# MB1297_RF_Module.net
KiCad netlist of a schematic drawn in Altium Designer
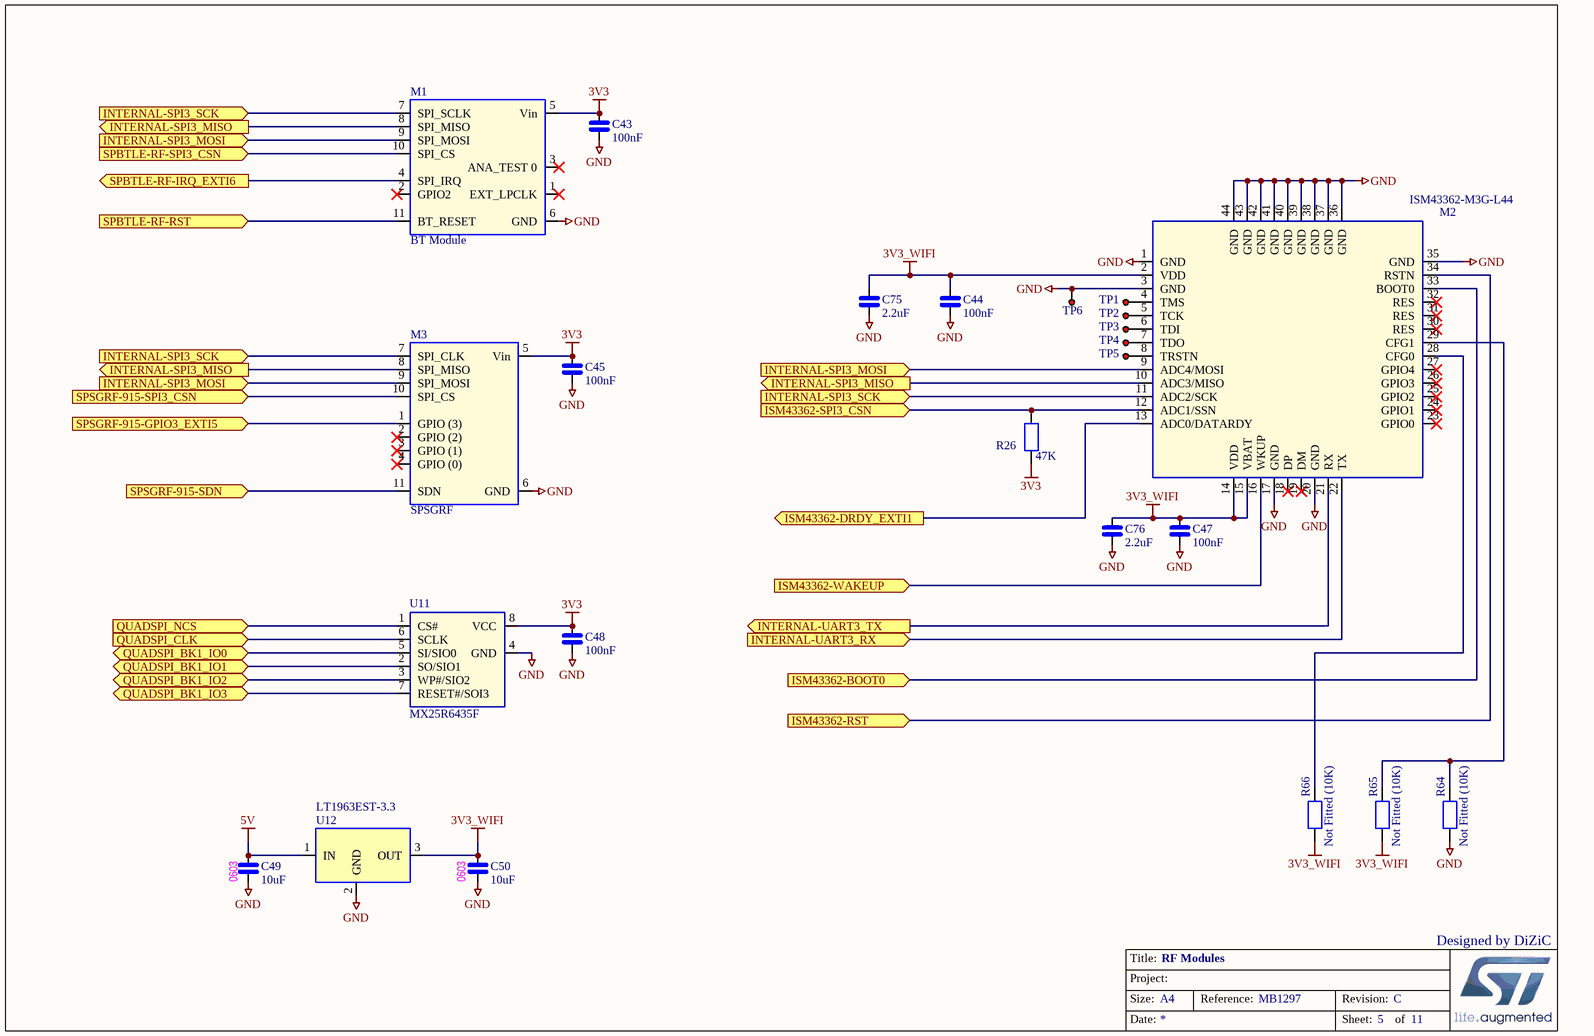
[diagram p0: MB1297_RF_Module.SchDoc]

(export (version "E")
  (design (tool "Eeschema 10.0.6"))
  (components
    (comp (ref "C43")
      (value "100nF")
      (footprint "0402_CAP_NPOL")
      (description "Capacitor_not polarized")
      (libsource (lib "ST_Lib3D") (part "CAP_NPOL"))
    )
    (comp (ref "C44")
      (value "100nF")
      (footprint "0402_CAP_NPOL")
      (description "Capacitor_not polarized")
      (libsource (lib "ST_Lib3D") (part "CAP_NPOL"))
    )
    (comp (ref "C45")
      (value "100nF")
      (footprint "0402_CAP_NPOL")
      (description "Capacitor_not polarized")
      (libsource (lib "ST_Lib3D") (part "CAP_NPOL"))
    )
    (comp (ref "C47")
      (value "100nF")
      (footprint "0402_CAP_NPOL")
      (description "Capacitor_not polarized")
      (libsource (lib "ST_Lib3D") (part "CAP_NPOL"))
    )
    (comp (ref "C48")
      (value "100nF")
      (footprint "0402_CAP_NPOL")
      (description "Capacitor_not polarized")
      (libsource (lib "ST_Lib3D") (part "CAP_NPOL"))
    )
    (comp (ref "C49")
      (value "10uF")
      (footprint "0603_CAP_NPOL")
      (description "Capacitor_not polarized")
      (libsource (lib "ST_Lib3D") (part "CAP_NPOL"))
    )
    (comp (ref "C50")
      (value "10uF")
      (footprint "0603_CAP_NPOL")
      (description "Capacitor_not polarized")
      (libsource (lib "ST_Lib3D") (part "CAP_NPOL"))
    )
    (comp (ref "C75")
      (value "2.2uF")
      (footprint "0603_CAP_NPOL")
      (description "Capacitor_not polarized")
      (libsource (lib "ST_Lib3D") (part "CAP_NPOL"))
    )
    (comp (ref "C76")
      (value "2.2uF")
      (footprint "0603_CAP_NPOL")
      (description "Capacitor_not polarized")
      (libsource (lib "ST_Lib3D") (part "CAP_NPOL"))
    )
    (comp (ref "M1")
      (value "BT Module")
      (footprint "SPBTLE-RF")
      (description "SPBTLE-RF")
      (libsource (lib "ST_Lib3D") (part "SPBTLE-RF"))
    )
    (comp (ref "M2")
      (value "ISM43362-M3G-L44")
      (footprint "ISM43362-M3G-L44")
      (description "ISM43362-M3G-L44 Wifi Module 802.11 bgn")
      (libsource (lib "Phil_Lib3D") (part "ISM43362-M3G-L44"))
    )
    (comp (ref "M3")
      (value "SPSGRF")
      (footprint "SPSGRF")
      (description "SPSGRF-915or SPSGRF-868")
      (libsource (lib "ST_Lib3D") (part "SPSGRF"))
    )
    (comp (ref "R26")
      (value "47K")
      (footprint "0402_RES")
      (description "Resistor")
      (libsource (lib "Lib3D_Altium10_Schlib") (part "RES"))
    )
    (comp (ref "R64")
      (value "Not Fitted (10K)")
      (footprint "0402_RES")
      (description "Resistor")
      (libsource (lib "Lib3D_Altium10_Schlib") (part "RES"))
    )
    (comp (ref "R65")
      (value "Not Fitted (10K)")
      (footprint "0402_RES")
      (description "Resistor")
      (libsource (lib "Lib3D_Altium10_Schlib") (part "RES"))
    )
    (comp (ref "R66")
      (value "Not Fitted (10K)")
      (footprint "0402_RES")
      (description "Resistor")
      (libsource (lib "Lib3D_Altium10_Schlib") (part "RES"))
    )
    (comp (ref "TP1")
      (value "PT")
      (footprint "PTB")
      (description "Point de test")
      (libsource (lib "ST_Lib2D") (part "PT"))
    )
    (comp (ref "TP2")
      (value "PT")
      (footprint "PTB")
      (description "Point de test")
      (libsource (lib "ST_Lib2D") (part "PT"))
    )
    (comp (ref "TP3")
      (value "PT")
      (footprint "PTB")
      (description "Point de test")
      (libsource (lib "ST_Lib2D") (part "PT"))
    )
    (comp (ref "TP4")
      (value "PT")
      (footprint "PTB")
      (description "Point de test")
      (libsource (lib "ST_Lib2D") (part "PT"))
    )
    (comp (ref "TP5")
      (value "PT")
      (footprint "PTB")
      (description "Point de test")
      (libsource (lib "ST_Lib2D") (part "PT"))
    )
    (comp (ref "TP6")
      (value "PT")
      (footprint "PTB")
      (description "Point de test")
      (libsource (lib "ST_Lib2D") (part "PT"))
    )
    (comp (ref "U11")
      (value "MX25R6435F")
      (footprint "SOP8L")
      (description "MX25R6435F Serial Flash Memory 64M")
      (libsource (lib "ST_Lib3D") (part "MX25R6435F"))
    )
    (comp (ref "U12")
      (value "LT1963EST-3.3")
      (footprint "ST_Lib3D:SOT223_SC73")
      (description "LT1963EST-3.3 LDO Low Noise 1.5A fast Transient Response")
      (libsource (lib "ST_Lib3D") (part "LT1963EST-3.3"))
    )
  )
  (nets
    (net (code "1") (name "/INTERNAL-SPI3_MISO") (class "Default")
      (node (ref "M1") (pin "8") (pinfunction "SPI_MISO_8") (pintype "passive"))
      (node (ref "M2") (pin "10") (pinfunction "ADC3/MISO_10") (pintype "passive"))
      (node (ref "M3") (pin "8") (pinfunction "SPI_MISO_8") (pintype "passive"))
    )
    (net (code "2") (name "/INTERNAL-SPI3_MOSI") (class "Default")
      (node (ref "M1") (pin "9") (pinfunction "SPI_MOSI_9") (pintype "passive"))
      (node (ref "M2") (pin "9") (pinfunction "ADC4/MOSI_9") (pintype "passive"))
      (node (ref "M3") (pin "9") (pinfunction "SPI_MOSI_9") (pintype "passive"))
    )
    (net (code "3") (name "/INTERNAL-SPI3_SCK") (class "Default")
      (node (ref "M1") (pin "7") (pinfunction "SPI_SCLK_7") (pintype "passive"))
      (node (ref "M2") (pin "11") (pinfunction "ADC2/SCK_11") (pintype "passive"))
      (node (ref "M3") (pin "7") (pinfunction "SPI_CLK_7") (pintype "passive"))
    )
    (net (code "4") (name "/INTERNAL-UART3_RX") (class "Default")
      (node (ref "M2") (pin "22") (pinfunction "TX_22") (pintype "passive"))
    )
    (net (code "5") (name "/INTERNAL-UART3_TX") (class "Default")
      (node (ref "M2") (pin "21") (pinfunction "RX_21") (pintype "passive"))
    )
    (net (code "6") (name "/ISM43362-BOOT0") (class "Default")
      (node (ref "M2") (pin "33") (pinfunction "BOOT0_33") (pintype "passive"))
    )
    (net (code "7") (name "/ISM43362-DRDY_EXTI1") (class "Default")
      (node (ref "M2") (pin "13") (pinfunction "ADC0/DATARDY_13") (pintype "passive"))
    )
    (net (code "8") (name "/ISM43362-RST") (class "Default")
      (node (ref "M2") (pin "34") (pinfunction "RSTN_34") (pintype "passive"))
    )
    (net (code "9") (name "/ISM43362-SPI3_CSN") (class "Default")
      (node (ref "M2") (pin "12") (pinfunction "ADC1/SSN_12") (pintype "passive"))
      (node (ref "R26") (pin "1") (pinfunction "1_1") (pintype "passive"))
    )
    (net (code "10") (name "/ISM43362-WAKEUP") (class "Default")
      (node (ref "M2") (pin "16") (pinfunction "WKUP_16") (pintype "passive"))
    )
    (net (code "11") (name "/QUADSPI_BK1_IO0") (class "Default")
      (node (ref "U11") (pin "5") (pinfunction "SI/SIO0_5") (pintype "passive"))
    )
    (net (code "12") (name "/QUADSPI_BK1_IO1") (class "Default")
      (node (ref "U11") (pin "2") (pinfunction "SO/SIO1_2") (pintype "passive"))
    )
    (net (code "13") (name "/QUADSPI_BK1_IO2") (class "Default")
      (node (ref "U11") (pin "3") (pinfunction "WP#/SIO2_3") (pintype "passive"))
    )
    (net (code "14") (name "/QUADSPI_BK1_IO3") (class "Default")
      (node (ref "U11") (pin "7") (pinfunction "RESET#/SOI3_7") (pintype "passive"))
    )
    (net (code "15") (name "/QUADSPI_CLK") (class "Default")
      (node (ref "U11") (pin "6") (pinfunction "SCLK_6") (pintype "passive"))
    )
    (net (code "16") (name "/QUADSPI_NCS") (class "Default")
      (node (ref "U11") (pin "1") (pinfunction "CS#_1") (pintype "passive"))
    )
    (net (code "17") (name "/SPBTLE-RF-IRQ_EXTI6") (class "Default")
      (node (ref "M1") (pin "4") (pinfunction "SPI_IRQ_4") (pintype "passive"))
    )
    (net (code "18") (name "/SPBTLE-RF-RST") (class "Default")
      (node (ref "M1") (pin "11") (pinfunction "BT_RESET_11") (pintype "passive"))
    )
    (net (code "19") (name "/SPBTLE-RF-SPI3_CSN") (class "Default")
      (node (ref "M1") (pin "10") (pinfunction "SPI_CS_10") (pintype "passive"))
    )
    (net (code "20") (name "/SPSGRF-915-GPIO3_EXTI5") (class "Default")
      (node (ref "M3") (pin "1") (pinfunction "GPIO_(3)_1") (pintype "passive"))
    )
    (net (code "21") (name "/SPSGRF-915-SDN") (class "Default")
      (node (ref "M3") (pin "11") (pinfunction "SDN_11") (pintype "passive"))
    )
    (net (code "22") (name "/SPSGRF-915-SPI3_CSN") (class "Default")
      (node (ref "M3") (pin "10") (pinfunction "SPI_CS_10") (pintype "passive"))
    )
    (net (code "23") (name "3V3") (class "Default")
      (node (ref "C43") (pin "1") (pinfunction "1_1") (pintype "passive"))
      (node (ref "C45") (pin "1") (pinfunction "1_1") (pintype "passive"))
      (node (ref "C48") (pin "1") (pinfunction "1_1") (pintype "passive"))
      (node (ref "M1") (pin "5") (pinfunction "Vin_5") (pintype "passive"))
      (node (ref "M3") (pin "5") (pinfunction "Vin_5") (pintype "passive"))
      (node (ref "R26") (pin "2") (pinfunction "2_2") (pintype "passive"))
      (node (ref "U11") (pin "8") (pinfunction "VCC_8") (pintype "passive"))
    )
    (net (code "24") (name "3V3_WIFI") (class "Default")
      (node (ref "C44") (pin "1") (pinfunction "1_1") (pintype "passive"))
      (node (ref "C47") (pin "1") (pinfunction "1_1") (pintype "passive"))
      (node (ref "C50") (pin "1") (pinfunction "1_1") (pintype "passive"))
      (node (ref "C75") (pin "1") (pinfunction "1_1") (pintype "passive"))
      (node (ref "C76") (pin "1") (pinfunction "1_1") (pintype "passive"))
      (node (ref "M2") (pin "14") (pinfunction "VDD_14") (pintype "passive"))
      (node (ref "M2") (pin "15") (pinfunction "VBAT_15") (pintype "passive"))
      (node (ref "M2") (pin "2") (pinfunction "VDD_2") (pintype "passive"))
      (node (ref "R65") (pin "2") (pinfunction "2_2") (pintype "passive"))
      (node (ref "R66") (pin "2") (pinfunction "2_2") (pintype "passive"))
      (node (ref "U12") (pin "3") (pinfunction "OUT_3") (pintype "passive"))
    )
    (net (code "25") (name "5V") (class "Default")
      (node (ref "C49") (pin "1") (pinfunction "1_1") (pintype "passive"))
      (node (ref "U12") (pin "1") (pinfunction "IN_1") (pintype "passive"))
    )
    (net (code "26") (name "GND") (class "Default")
      (node (ref "C43") (pin "2") (pinfunction "2_2") (pintype "passive"))
      (node (ref "C44") (pin "2") (pinfunction "2_2") (pintype "passive"))
      (node (ref "C45") (pin "2") (pinfunction "2_2") (pintype "passive"))
      (node (ref "C47") (pin "2") (pinfunction "2_2") (pintype "passive"))
      (node (ref "C48") (pin "2") (pinfunction "2_2") (pintype "passive"))
      (node (ref "C49") (pin "2") (pinfunction "2_2") (pintype "passive"))
      (node (ref "C50") (pin "2") (pinfunction "2_2") (pintype "passive"))
      (node (ref "C75") (pin "2") (pinfunction "2_2") (pintype "passive"))
      (node (ref "C76") (pin "2") (pinfunction "2_2") (pintype "passive"))
      (node (ref "M1") (pin "6") (pinfunction "GND_6") (pintype "passive"))
      (node (ref "M2") (pin "1") (pinfunction "GND_1") (pintype "passive"))
      (node (ref "M2") (pin "17") (pinfunction "GND_17") (pintype "passive"))
      (node (ref "M2") (pin "20") (pinfunction "GND_20") (pintype "passive"))
      (node (ref "M2") (pin "3") (pinfunction "GND_3") (pintype "passive"))
      (node (ref "M2") (pin "35") (pinfunction "GND_35") (pintype "passive"))
      (node (ref "M2") (pin "36") (pinfunction "GND_36") (pintype "passive"))
      (node (ref "M2") (pin "37") (pinfunction "GND_37") (pintype "passive"))
      (node (ref "M2") (pin "38") (pinfunction "GND_38") (pintype "passive"))
      (node (ref "M2") (pin "39") (pinfunction "GND_39") (pintype "passive"))
      (node (ref "M2") (pin "40") (pinfunction "GND_40") (pintype "passive"))
      (node (ref "M2") (pin "41") (pinfunction "GND_41") (pintype "passive"))
      (node (ref "M2") (pin "42") (pinfunction "GND_42") (pintype "passive"))
      (node (ref "M2") (pin "43") (pinfunction "GND_43") (pintype "passive"))
      (node (ref "M2") (pin "44") (pinfunction "GND_44") (pintype "passive"))
      (node (ref "M3") (pin "6") (pinfunction "GND_6") (pintype "passive"))
      (node (ref "R64") (pin "2") (pinfunction "2_2") (pintype "passive"))
      (node (ref "TP6") (pin "1") (pintype "passive"))
      (node (ref "U11") (pin "4") (pinfunction "GND_4") (pintype "passive"))
      (node (ref "U12") (pin "2") (pinfunction "GND_2") (pintype "passive"))
    )
    (net (code "27") (name "Net-(M2-CFG0)") (class "Default")
      (node (ref "M2") (pin "28") (pinfunction "CFG0_28") (pintype "passive"))
      (node (ref "R66") (pin "1") (pinfunction "1_1") (pintype "passive"))
    )
    (net (code "28") (name "Net-(M2-CFG1)") (class "Default")
      (node (ref "M2") (pin "29") (pinfunction "CFG1_29") (pintype "passive"))
      (node (ref "R64") (pin "1") (pinfunction "1_1") (pintype "passive"))
      (node (ref "R65") (pin "1") (pinfunction "1_1") (pintype "passive"))
    )
    (net (code "29") (name "Net-(M2-TCK)") (class "Default")
      (node (ref "M2") (pin "5") (pinfunction "TCK_5") (pintype "passive"))
      (node (ref "TP2") (pin "1") (pintype "passive"))
    )
    (net (code "30") (name "Net-(M2-TDI)") (class "Default")
      (node (ref "M2") (pin "6") (pinfunction "TDI_6") (pintype "passive"))
      (node (ref "TP3") (pin "1") (pintype "passive"))
    )
    (net (code "31") (name "Net-(M2-TDO)") (class "Default")
      (node (ref "M2") (pin "7") (pinfunction "TDO_7") (pintype "passive"))
      (node (ref "TP4") (pin "1") (pintype "passive"))
    )
    (net (code "32") (name "Net-(M2-TMS)") (class "Default")
      (node (ref "M2") (pin "4") (pinfunction "TMS_4") (pintype "passive"))
      (node (ref "TP1") (pin "1") (pintype "passive"))
    )
    (net (code "33") (name "Net-(M2-TRSTN)") (class "Default")
      (node (ref "M2") (pin "8") (pinfunction "TRSTN_8") (pintype "passive"))
      (node (ref "TP5") (pin "1") (pintype "passive"))
    )
    (net (code "34") (name "unconnected-(M1-ANA_TEST_0-Pad3)") (class "Default")
      (node (ref "M1") (pin "3") (pinfunction "ANA_TEST_0_3") (pintype "passive+no_connect"))
    )
    (net (code "35") (name "unconnected-(M1-EXT_LPCLK-Pad1)") (class "Default")
      (node (ref "M1") (pin "1") (pinfunction "EXT_LPCLK_1") (pintype "passive+no_connect"))
    )
    (net (code "36") (name "unconnected-(M1-GPIO2-Pad2)") (class "Default")
      (node (ref "M1") (pin "2") (pinfunction "GPIO2_2") (pintype "passive+no_connect"))
    )
    (net (code "37") (name "unconnected-(M2-DM-Pad19)") (class "Default")
      (node (ref "M2") (pin "19") (pinfunction "DM_19") (pintype "passive+no_connect"))
    )
    (net (code "38") (name "unconnected-(M2-DP-Pad18)") (class "Default")
      (node (ref "M2") (pin "18") (pinfunction "DP_18") (pintype "passive+no_connect"))
    )
    (net (code "39") (name "unconnected-(M2-GPIO0-Pad23)") (class "Default")
      (node (ref "M2") (pin "23") (pinfunction "GPIO0_23") (pintype "passive+no_connect"))
    )
    (net (code "40") (name "unconnected-(M2-GPIO1-Pad24)") (class "Default")
      (node (ref "M2") (pin "24") (pinfunction "GPIO1_24") (pintype "passive+no_connect"))
    )
    (net (code "41") (name "unconnected-(M2-GPIO2-Pad25)") (class "Default")
      (node (ref "M2") (pin "25") (pinfunction "GPIO2_25") (pintype "passive+no_connect"))
    )
    (net (code "42") (name "unconnected-(M2-GPIO3-Pad26)") (class "Default")
      (node (ref "M2") (pin "26") (pinfunction "GPIO3_26") (pintype "passive+no_connect"))
    )
    (net (code "43") (name "unconnected-(M2-GPIO4-Pad27)") (class "Default")
      (node (ref "M2") (pin "27") (pinfunction "GPIO4_27") (pintype "passive+no_connect"))
    )
    (net (code "44") (name "unconnected-(M2-RES-Pad30)") (class "Default")
      (node (ref "M2") (pin "30") (pinfunction "RES_30") (pintype "passive+no_connect"))
    )
    (net (code "45") (name "unconnected-(M2-RES-Pad31)") (class "Default")
      (node (ref "M2") (pin "31") (pinfunction "RES_31") (pintype "passive+no_connect"))
    )
    (net (code "46") (name "unconnected-(M2-RES-Pad32)") (class "Default")
      (node (ref "M2") (pin "32") (pinfunction "RES_32") (pintype "passive+no_connect"))
    )
    (net (code "47") (name "unconnected-(M3-GPIO_(0)-Pad4)") (class "Default")
      (node (ref "M3") (pin "4") (pinfunction "GPIO_(0)_4") (pintype "passive+no_connect"))
    )
    (net (code "48") (name "unconnected-(M3-GPIO_(1)-Pad3)") (class "Default")
      (node (ref "M3") (pin "3") (pinfunction "GPIO_(1)_3") (pintype "passive+no_connect"))
    )
    (net (code "49") (name "unconnected-(M3-GPIO_(2)-Pad2)") (class "Default")
      (node (ref "M3") (pin "2") (pinfunction "GPIO_(2)_2") (pintype "passive+no_connect"))
    )
  )
)
